# 1_-Controller_Page.net
KiCad netlist of a schematic drawn in Altium Designer
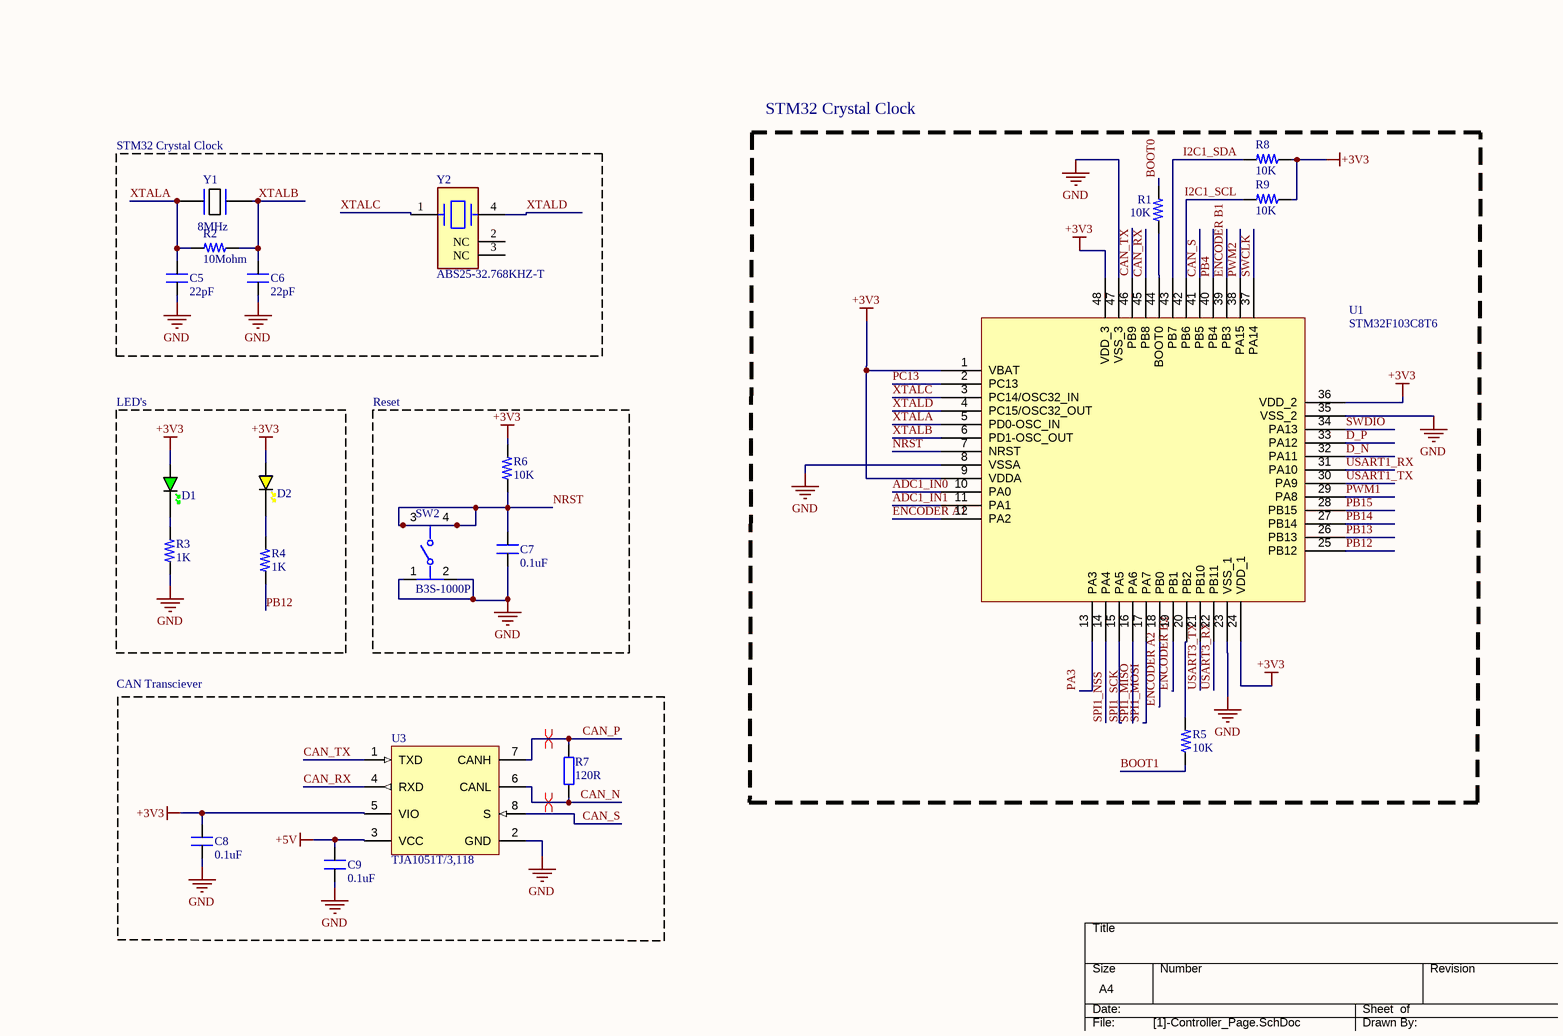
[diagram p0: [1]-Controller_Page.SchDoc]

(export (version "E")
  (design (tool "Eeschema 10.0.6"))
  (components
    (comp (ref "C5")
      (value "22pF")
      (footprint "CAP_0805")
      (description "22pF ±5% 50V Ceramic Capacitor C0G, NP0 0805 (2012 Metric)")
      (fields
        (field (name "MANUFACTURER") "KEMET")
        (field (name "MANUFACTURER PART NUMBER") "C0805C220J5GACTU")
      )
      (libsource (lib "STM_SCH_LIB") (part "CAP_22pF-50V-5%-0805"))
    )
    (comp (ref "C6")
      (value "22pF")
      (footprint "CAP_0805")
      (description "22pF ±5% 50V Ceramic Capacitor C0G, NP0 0805 (2012 Metric)")
      (fields
        (field (name "MANUFACTURER") "KEMET")
        (field (name "MANUFACTURER PART NUMBER") "C0805C220J5GACTU")
      )
      (libsource (lib "STM_SCH_LIB") (part "CAP_22pF-50V-5%-0805"))
    )
    (comp (ref "C7")
      (value "0.1uF")
      (footprint "CAP_0805")
      (description "0.1µF ±5% 50V Ceramic Capacitor X7R 0805 (2012 Metric)")
      (fields
        (field (name "MANUFACTURER") "KEMET")
        (field (name "MANUFACTURING PART NUMBER") "C0805C104J5RACTU")
      )
      (libsource (lib "STM_SCH_LIB") (part "CAP_0.1uF-50V-5%-0805"))
    )
    (comp (ref "C8")
      (value "0.1uF")
      (footprint "CAP_0805")
      (description "0.1µF ±5% 50V Ceramic Capacitor X7R 0805 (2012 Metric)")
      (fields
        (field (name "MANUFACTURER") "KEMET")
        (field (name "MANUFACTURING PART NUMBER") "C0805C104J5RACTU")
      )
      (libsource (lib "STM_SCH_LIB") (part "CAP_0.1uF-50V-5%-0805"))
    )
    (comp (ref "C9")
      (value "0.1uF")
      (footprint "CAP_0805")
      (description "0.1µF ±5% 50V Ceramic Capacitor X7R 0805 (2012 Metric)")
      (fields
        (field (name "MANUFACTURER") "KEMET")
        (field (name "MANUFACTURING PART NUMBER") "C0805C104J5RACTU")
      )
      (libsource (lib "STM_SCH_LIB") (part "CAP_0.1uF-50V-5%-0805"))
    )
    (comp (ref "D1")
      (value "GREEN")
      (footprint "LED_0402_GREEN")
      (description "LED 0402 GREEN SMD")
      (libsource (lib "Schematic-Lib-PhilsLab") (part "LED_0402_GREEN"))
    )
    (comp (ref "D2")
      (value "YELLOW")
      (footprint "LED_0402_YELLOW")
      (description "LED 0402 YELLOW SMD")
      (libsource (lib "Schematic-Lib-PhilsLab") (part "LED_0402_YELLOW"))
    )
    (comp (ref "R1")
      (value "10K")
      (footprint "RES_0805")
      (description "10 kOhms ±1% 0.125W, 1/8W Chip Resistor 0805 (2012 Metric) Moisture Resistant Thick Film")
      (fields
        (field (name "MANUFACTURER") "Yageo")
        (field (name "MANUFACTURING PART NUMBER") "RC0805FR-0710KL")
      )
      (libsource (lib "STM_SCH_LIB") (part "RES_10K-0.125W-1%-0805"))
    )
    (comp (ref "R2")
      (value "10Mohm")
      (footprint "RES_0805")
      (fields
        (field (name "MANUFACTURER") "Rohm Semiconductor")
        (field (name "MANUFACTURING PART NUMBER") "KTR10EZPF1005")
      )
      (libsource (lib "STM_SCH_LIB") (part "RES_10MOHM-0.125W-1%-0805"))
    )
    (comp (ref "R3")
      (value "1K")
      (footprint "RES_0805")
      (description "1 kOhms ±1% 0.125W, 1/8W Chip Resistor 0805 (2012 Metric) Moisture Resistant Thick Film")
      (fields (field (name "MANUFACTURER") "垈㎵á") (field (name "MANUFACTURER PART NUMBER") "RC0805FR-071KL"))
      (libsource (lib "STM_SCH_LIB") (part "RES_1K-0.125W-1%-0805"))
    )
    (comp (ref "R4")
      (value "1K")
      (footprint "RES_0805")
      (description "1 kOhms ±1% 0.125W, 1/8W Chip Resistor 0805 (2012 Metric) Moisture Resistant Thick Film")
      (fields (field (name "MANUFACTURER") "垈㎵á") (field (name "MANUFACTURER PART NUMBER") "RC0805FR-071KL"))
      (libsource (lib "STM_SCH_LIB") (part "RES_1K-0.125W-1%-0805"))
    )
    (comp (ref "R5")
      (value "10K")
      (footprint "RES_0805")
      (description "10 kOhms ±1% 0.125W, 1/8W Chip Resistor 0805 (2012 Metric) Moisture Resistant Thick Film")
      (fields
        (field (name "MANUFACTURER") "Yageo")
        (field (name "MANUFACTURING PART NUMBER") "RC0805FR-0710KL")
      )
      (libsource (lib "STM_SCH_LIB") (part "RES_10K-0.125W-1%-0805"))
    )
    (comp (ref "R6")
      (value "10K")
      (footprint "RES_0805")
      (description "10 kOhms ±1% 0.125W, 1/8W Chip Resistor 0805 (2012 Metric) Moisture Resistant Thick Film")
      (fields
        (field (name "MANUFACTURER") "Yageo")
        (field (name "MANUFACTURING PART NUMBER") "RC0805FR-0710KL")
      )
      (libsource (lib "STM_SCH_LIB") (part "RES_10K-0.125W-1%-0805"))
    )
    (comp (ref "R7")
      (value "120R")
      (footprint "RES_0805")
      (description "Resistor SMD 0805")
      (libsource (lib "Schematic-Lib-PhilsLab") (part "RES_0805"))
    )
    (comp (ref "R8")
      (value "10K")
      (footprint "RES_0805")
      (description "10 kOhms ±1% 0.125W, 1/8W Chip Resistor 0805 (2012 Metric) Moisture Resistant Thick Film")
      (fields
        (field (name "MANUFACTURER") "Yageo")
        (field (name "MANUFACTURING PART NUMBER") "RC0805FR-0710KL")
      )
      (libsource (lib "STM_SCH_LIB") (part "RES_10K-0.125W-1%-0805"))
    )
    (comp (ref "R9")
      (value "10K")
      (footprint "RES_0805")
      (description "10 kOhms ±1% 0.125W, 1/8W Chip Resistor 0805 (2012 Metric) Moisture Resistant Thick Film")
      (fields
        (field (name "MANUFACTURER") "Yageo")
        (field (name "MANUFACTURING PART NUMBER") "RC0805FR-0710KL")
      )
      (libsource (lib "STM_SCH_LIB") (part "RES_10K-0.125W-1%-0805"))
    )
    (comp (ref "SW2")
      (value "B3S-1000P")
      (footprint "FP-B3S-1000P-MFG")
      (description "SWITCH TACTILE SPST-NO 0.05A 24V")
      (libsource (lib "Altium Content Vault") (part "b8895f3f4cefb76e1819d2863dba89b"))
    )
    (comp (ref "U1")
      (value "STM32F103C8T6")
      (footprint "LQFP-48_19.6_393_58X11_SMD")
      (description "ARM® Cortex®-M3 STM32F1 Microcontroller IC 32-Bit 72MHz 64KB (64K x 8) FLASH")
      (fields (field (name "MANUFACTURER") "STMicroelectronics"))
      (libsource (lib "STM_SCH_LIB") (part "IC-STM32F103C8T6 _1"))
    )
    (comp (ref "U3")
      (value "TJA1051T/3,118")
      (footprint "NXP-SOIC-8_L")
      (description "High-Speed CAN Transceiver, 3 to 5 V, 8-Pin SOIC (SOT96-1), RoHS, Tape and Reel")
      (fields (field (name "MANUFACTURER") "NXP"))
      (libsource (lib "Altium Content Vault") (part "NXP-TJA1051T_3-SOIC-8"))
    )
    (comp (ref "Y1")
      (value "8MHz")
      (footprint "XTAL_314_240X47_SMD")
      (description "Crystals 8MHz 22pF -20C 70C")
      (fields
        (field (name "MANUFACTURER") "IQD Frequency Products")
        (field (name "MANUFACTURING PART NUMBER") "LFXTAL030234Reel")
      )
      (libsource (lib "STM_SCH_LIB") (part "XTAL_8MHZ-LFXTAL030234"))
    )
    (comp (ref "Y2")
      (value "ABS25-32.768KHZ-T")
      (footprint "FP-ABS25-MFG")
      (description "CRYSTAL 32.7680KHZ 12.5PF SMD")
      (fields (field (name "TOLERANCE") "20ppm"))
      (libsource (lib "Altium Content Vault") (part "d2378e42ab3755ffcd472789242ec61"))
    )
  )
  (nets
    (net (code "1") (name "+3V3") (class "Default")
      (node (ref "C8") (pin "2") (pinfunction "2_2") (pintype "passive"))
      (node (ref "D1") (pin "A") (pinfunction "A_A") (pintype "passive"))
      (node (ref "D2") (pin "A") (pinfunction "A_A") (pintype "passive"))
      (node (ref "R6") (pin "2") (pinfunction "2_2") (pintype "passive"))
      (node (ref "R8") (pin "2") (pinfunction "2_2") (pintype "passive"))
      (node (ref "R9") (pin "2") (pinfunction "2_2") (pintype "passive"))
      (node (ref "U1") (pin "1") (pinfunction "VBAT_1") (pintype "passive"))
      (node (ref "U1") (pin "24") (pinfunction "VDD_1_24") (pintype "passive"))
      (node (ref "U1") (pin "36") (pinfunction "VDD_2_36") (pintype "passive"))
      (node (ref "U1") (pin "48") (pinfunction "VDD_3_48") (pintype "passive"))
      (node (ref "U1") (pin "9") (pinfunction "VDDA_9") (pintype "passive"))
      (node (ref "U3") (pin "5") (pinfunction "VIO_5") (pintype "power_in"))
    )
    (net (code "2") (name "+5V") (class "Default")
      (node (ref "C9") (pin "2") (pinfunction "2_2") (pintype "passive"))
      (node (ref "U3") (pin "3") (pinfunction "VCC_3") (pintype "power_in"))
    )
    (net (code "3") (name "/ADC1_IN0") (class "Default")
      (node (ref "U1") (pin "10") (pinfunction "PA0_10") (pintype "passive"))
    )
    (net (code "4") (name "/ADC1_IN1") (class "Default")
      (node (ref "U1") (pin "11") (pinfunction "PA1_11") (pintype "passive"))
    )
    (net (code "5") (name "/BOOT0") (class "Default")
      (node (ref "R1") (pin "2") (pinfunction "2_2") (pintype "passive"))
    )
    (net (code "6") (name "/BOOT1") (class "Default")
      (node (ref "R5") (pin "2") (pinfunction "2_2") (pintype "passive"))
    )
    (net (code "7") (name "/CAN_N") (class "Default")
      (node (ref "R7") (pin "1") (pinfunction "1_1") (pintype "passive"))
      (node (ref "U3") (pin "6") (pinfunction "CANL_6") (pintype "passive"))
    )
    (net (code "8") (name "/CAN_P") (class "Default")
      (node (ref "R7") (pin "2") (pinfunction "2_2") (pintype "passive"))
      (node (ref "U3") (pin "7") (pinfunction "CANH_7") (pintype "passive"))
    )
    (net (code "9") (name "/CAN_RX") (class "Default")
      (node (ref "U1") (pin "45") (pinfunction "PB8_45") (pintype "passive"))
      (node (ref "U3") (pin "4") (pinfunction "RXD_4") (pintype "output"))
    )
    (net (code "10") (name "/CAN_S") (class "Default")
      (node (ref "U1") (pin "41") (pinfunction "PB5_41") (pintype "passive"))
      (node (ref "U3") (pin "8") (pinfunction "S_8") (pintype "input"))
    )
    (net (code "11") (name "/CAN_TX") (class "Default")
      (node (ref "U1") (pin "46") (pinfunction "PB9_46") (pintype "passive"))
      (node (ref "U3") (pin "1") (pinfunction "TXD_1") (pintype "input"))
    )
    (net (code "12") (name "/D_N") (class "Default")
      (node (ref "U1") (pin "32") (pinfunction "PA11_32") (pintype "passive"))
    )
    (net (code "13") (name "/D_P") (class "Default")
      (node (ref "U1") (pin "33") (pinfunction "PA12_33") (pintype "passive"))
    )
    (net (code "14") (name "/ENCODER A1") (class "Default")
      (node (ref "U1") (pin "12") (pinfunction "PA2_12") (pintype "passive"))
    )
    (net (code "15") (name "/ENCODER A2") (class "Default")
      (node (ref "U1") (pin "18") (pinfunction "PB0_18") (pintype "passive"))
    )
    (net (code "16") (name "/ENCODER B1") (class "Default")
      (node (ref "U1") (pin "39") (pinfunction "PB3_39") (pintype "passive"))
    )
    (net (code "17") (name "/ENCODER B2") (class "Default")
      (node (ref "U1") (pin "19") (pinfunction "PB1_19") (pintype "passive"))
    )
    (net (code "18") (name "/I2C1_SCL") (class "Default")
      (node (ref "R9") (pin "1") (pinfunction "1_1") (pintype "passive"))
      (node (ref "U1") (pin "42") (pinfunction "PB6_42") (pintype "passive"))
    )
    (net (code "19") (name "/I2C1_SDA") (class "Default")
      (node (ref "R8") (pin "1") (pinfunction "1_1") (pintype "passive"))
      (node (ref "U1") (pin "43") (pinfunction "PB7_43") (pintype "passive"))
    )
    (net (code "20") (name "/NRST") (class "Default")
      (node (ref "C7") (pin "2") (pinfunction "2_2") (pintype "passive"))
      (node (ref "R6") (pin "1") (pinfunction "1_1") (pintype "passive"))
      (node (ref "SW2") (pin "3") (pinfunction "3_3") (pintype "passive"))
      (node (ref "SW2") (pin "4") (pinfunction "4_4") (pintype "passive"))
      (node (ref "U1") (pin "7") (pinfunction "NRST_7") (pintype "passive"))
    )
    (net (code "21") (name "/PA3") (class "Default")
      (node (ref "U1") (pin "13") (pinfunction "PA3_13") (pintype "passive"))
    )
    (net (code "22") (name "/PB4") (class "Default")
      (node (ref "U1") (pin "40") (pinfunction "PB4_40") (pintype "passive"))
    )
    (net (code "23") (name "/PB12") (class "Default")
      (node (ref "R4") (pin "1") (pinfunction "1_1") (pintype "passive"))
      (node (ref "U1") (pin "25") (pinfunction "PB12_25") (pintype "passive"))
    )
    (net (code "24") (name "/PB13") (class "Default")
      (node (ref "U1") (pin "26") (pinfunction "PB13_26") (pintype "passive"))
    )
    (net (code "25") (name "/PB14") (class "Default")
      (node (ref "U1") (pin "27") (pinfunction "PB14_27") (pintype "passive"))
    )
    (net (code "26") (name "/PB15") (class "Default")
      (node (ref "U1") (pin "28") (pinfunction "PB15_28") (pintype "passive"))
    )
    (net (code "27") (name "/PC13") (class "Default")
      (node (ref "U1") (pin "2") (pinfunction "PC13_2") (pintype "passive"))
    )
    (net (code "28") (name "/PWM1") (class "Default")
      (node (ref "U1") (pin "29") (pinfunction "PA8_29") (pintype "passive"))
    )
    (net (code "29") (name "/PWM2") (class "Default")
      (node (ref "U1") (pin "38") (pinfunction "PA15_38") (pintype "passive"))
    )
    (net (code "30") (name "/SPI1_MISO") (class "Default")
      (node (ref "U1") (pin "16") (pinfunction "PA6_16") (pintype "passive"))
    )
    (net (code "31") (name "/SPI1_MOSI") (class "Default")
      (node (ref "U1") (pin "17") (pinfunction "PA7_17") (pintype "passive"))
    )
    (net (code "32") (name "/SPI1_NSS") (class "Default")
      (node (ref "U1") (pin "14") (pinfunction "PA4_14") (pintype "passive"))
    )
    (net (code "33") (name "/SPI1_SCK") (class "Default")
      (node (ref "U1") (pin "15") (pinfunction "PA5_15") (pintype "passive"))
    )
    (net (code "34") (name "/SWCLK") (class "Default")
      (node (ref "U1") (pin "37") (pinfunction "PA14_37") (pintype "passive"))
    )
    (net (code "35") (name "/SWDIO") (class "Default")
      (node (ref "U1") (pin "34") (pinfunction "PA13_34") (pintype "passive"))
    )
    (net (code "36") (name "/USART1_RX") (class "Default")
      (node (ref "U1") (pin "31") (pinfunction "PA10_31") (pintype "passive"))
    )
    (net (code "37") (name "/USART1_TX") (class "Default")
      (node (ref "U1") (pin "30") (pinfunction "PA9_30") (pintype "passive"))
    )
    (net (code "38") (name "/USART3_RX") (class "Default")
      (node (ref "U1") (pin "22") (pinfunction "PB11_22") (pintype "passive"))
    )
    (net (code "39") (name "/USART3_TX") (class "Default")
      (node (ref "U1") (pin "21") (pinfunction "PB10_21") (pintype "passive"))
    )
    (net (code "40") (name "/XTALA") (class "Default")
      (node (ref "C5") (pin "2") (pinfunction "2_2") (pintype "passive"))
      (node (ref "R2") (pin "1") (pinfunction "1_1") (pintype "passive"))
      (node (ref "U1") (pin "5") (pinfunction "PD0-OSC_IN_5") (pintype "passive"))
      (node (ref "Y1") (pin "1") (pinfunction "1_1") (pintype "passive"))
    )
    (net (code "41") (name "/XTALB") (class "Default")
      (node (ref "C6") (pin "2") (pinfunction "2_2") (pintype "passive"))
      (node (ref "R2") (pin "2") (pinfunction "2_2") (pintype "passive"))
      (node (ref "U1") (pin "6") (pinfunction "PD1-OSC_OUT_6") (pintype "passive"))
      (node (ref "Y1") (pin "2") (pinfunction "2_2") (pintype "passive"))
    )
    (net (code "42") (name "/XTALC") (class "Default")
      (node (ref "U1") (pin "3") (pinfunction "PC14/OSC32_IN_3") (pintype "passive"))
      (node (ref "Y2") (pin "1") (pinfunction "1_1") (pintype "passive"))
    )
    (net (code "43") (name "/XTALD") (class "Default")
      (node (ref "U1") (pin "4") (pinfunction "PC15/OSC32_OUT_4") (pintype "passive"))
      (node (ref "Y2") (pin "4") (pinfunction "4_4") (pintype "passive"))
    )
    (net (code "44") (name "GND") (class "Default")
      (node (ref "C5") (pin "1") (pinfunction "1_1") (pintype "passive"))
      (node (ref "C6") (pin "1") (pinfunction "1_1") (pintype "passive"))
      (node (ref "C7") (pin "1") (pinfunction "1_1") (pintype "passive"))
      (node (ref "C8") (pin "1") (pinfunction "1_1") (pintype "passive"))
      (node (ref "C9") (pin "1") (pinfunction "1_1") (pintype "passive"))
      (node (ref "R3") (pin "1") (pinfunction "1_1") (pintype "passive"))
      (node (ref "SW2") (pin "1") (pinfunction "1_1") (pintype "passive"))
      (node (ref "SW2") (pin "2") (pinfunction "2_2") (pintype "passive"))
      (node (ref "U1") (pin "23") (pinfunction "VSS_1_23") (pintype "passive"))
      (node (ref "U1") (pin "35") (pinfunction "VSS_2_35") (pintype "passive"))
      (node (ref "U1") (pin "47") (pinfunction "VSS_3_47") (pintype "passive"))
      (node (ref "U1") (pin "8") (pinfunction "VSSA_8") (pintype "passive"))
      (node (ref "U3") (pin "2") (pinfunction "GND_2") (pintype "power_in"))
    )
    (net (code "45") (name "Net-(D1-PadK)") (class "Default")
      (node (ref "D1") (pin "K") (pinfunction "K_K") (pintype "passive"))
      (node (ref "R3") (pin "2") (pinfunction "2_2") (pintype "passive"))
    )
    (net (code "46") (name "Net-(D2-PadK)") (class "Default")
      (node (ref "D2") (pin "K") (pinfunction "K_K") (pintype "passive"))
      (node (ref "R4") (pin "2") (pinfunction "2_2") (pintype "passive"))
    )
    (net (code "47") (name "Net-(U1-BOOT0)") (class "Default")
      (node (ref "R1") (pin "1") (pinfunction "1_1") (pintype "passive"))
      (node (ref "U1") (pin "44") (pinfunction "BOOT0_44") (pintype "passive"))
    )
    (net (code "48") (name "Net-(U1-PB2)") (class "Default")
      (node (ref "R5") (pin "1") (pinfunction "1_1") (pintype "passive"))
      (node (ref "U1") (pin "20") (pinfunction "PB2_20") (pintype "passive"))
    )
    (net (code "49") (name "unconnected-(Y2-NC-Pad2)") (class "Default")
      (node (ref "Y2") (pin "2") (pinfunction "NC_2") (pintype "passive"))
    )
    (net (code "50") (name "unconnected-(Y2-NC-Pad3)") (class "Default")
      (node (ref "Y2") (pin "3") (pinfunction "NC_3") (pintype "passive"))
    )
  )
)
